# Flyback_schematic.net
KiCad netlist of a schematic drawn in Altium Designer
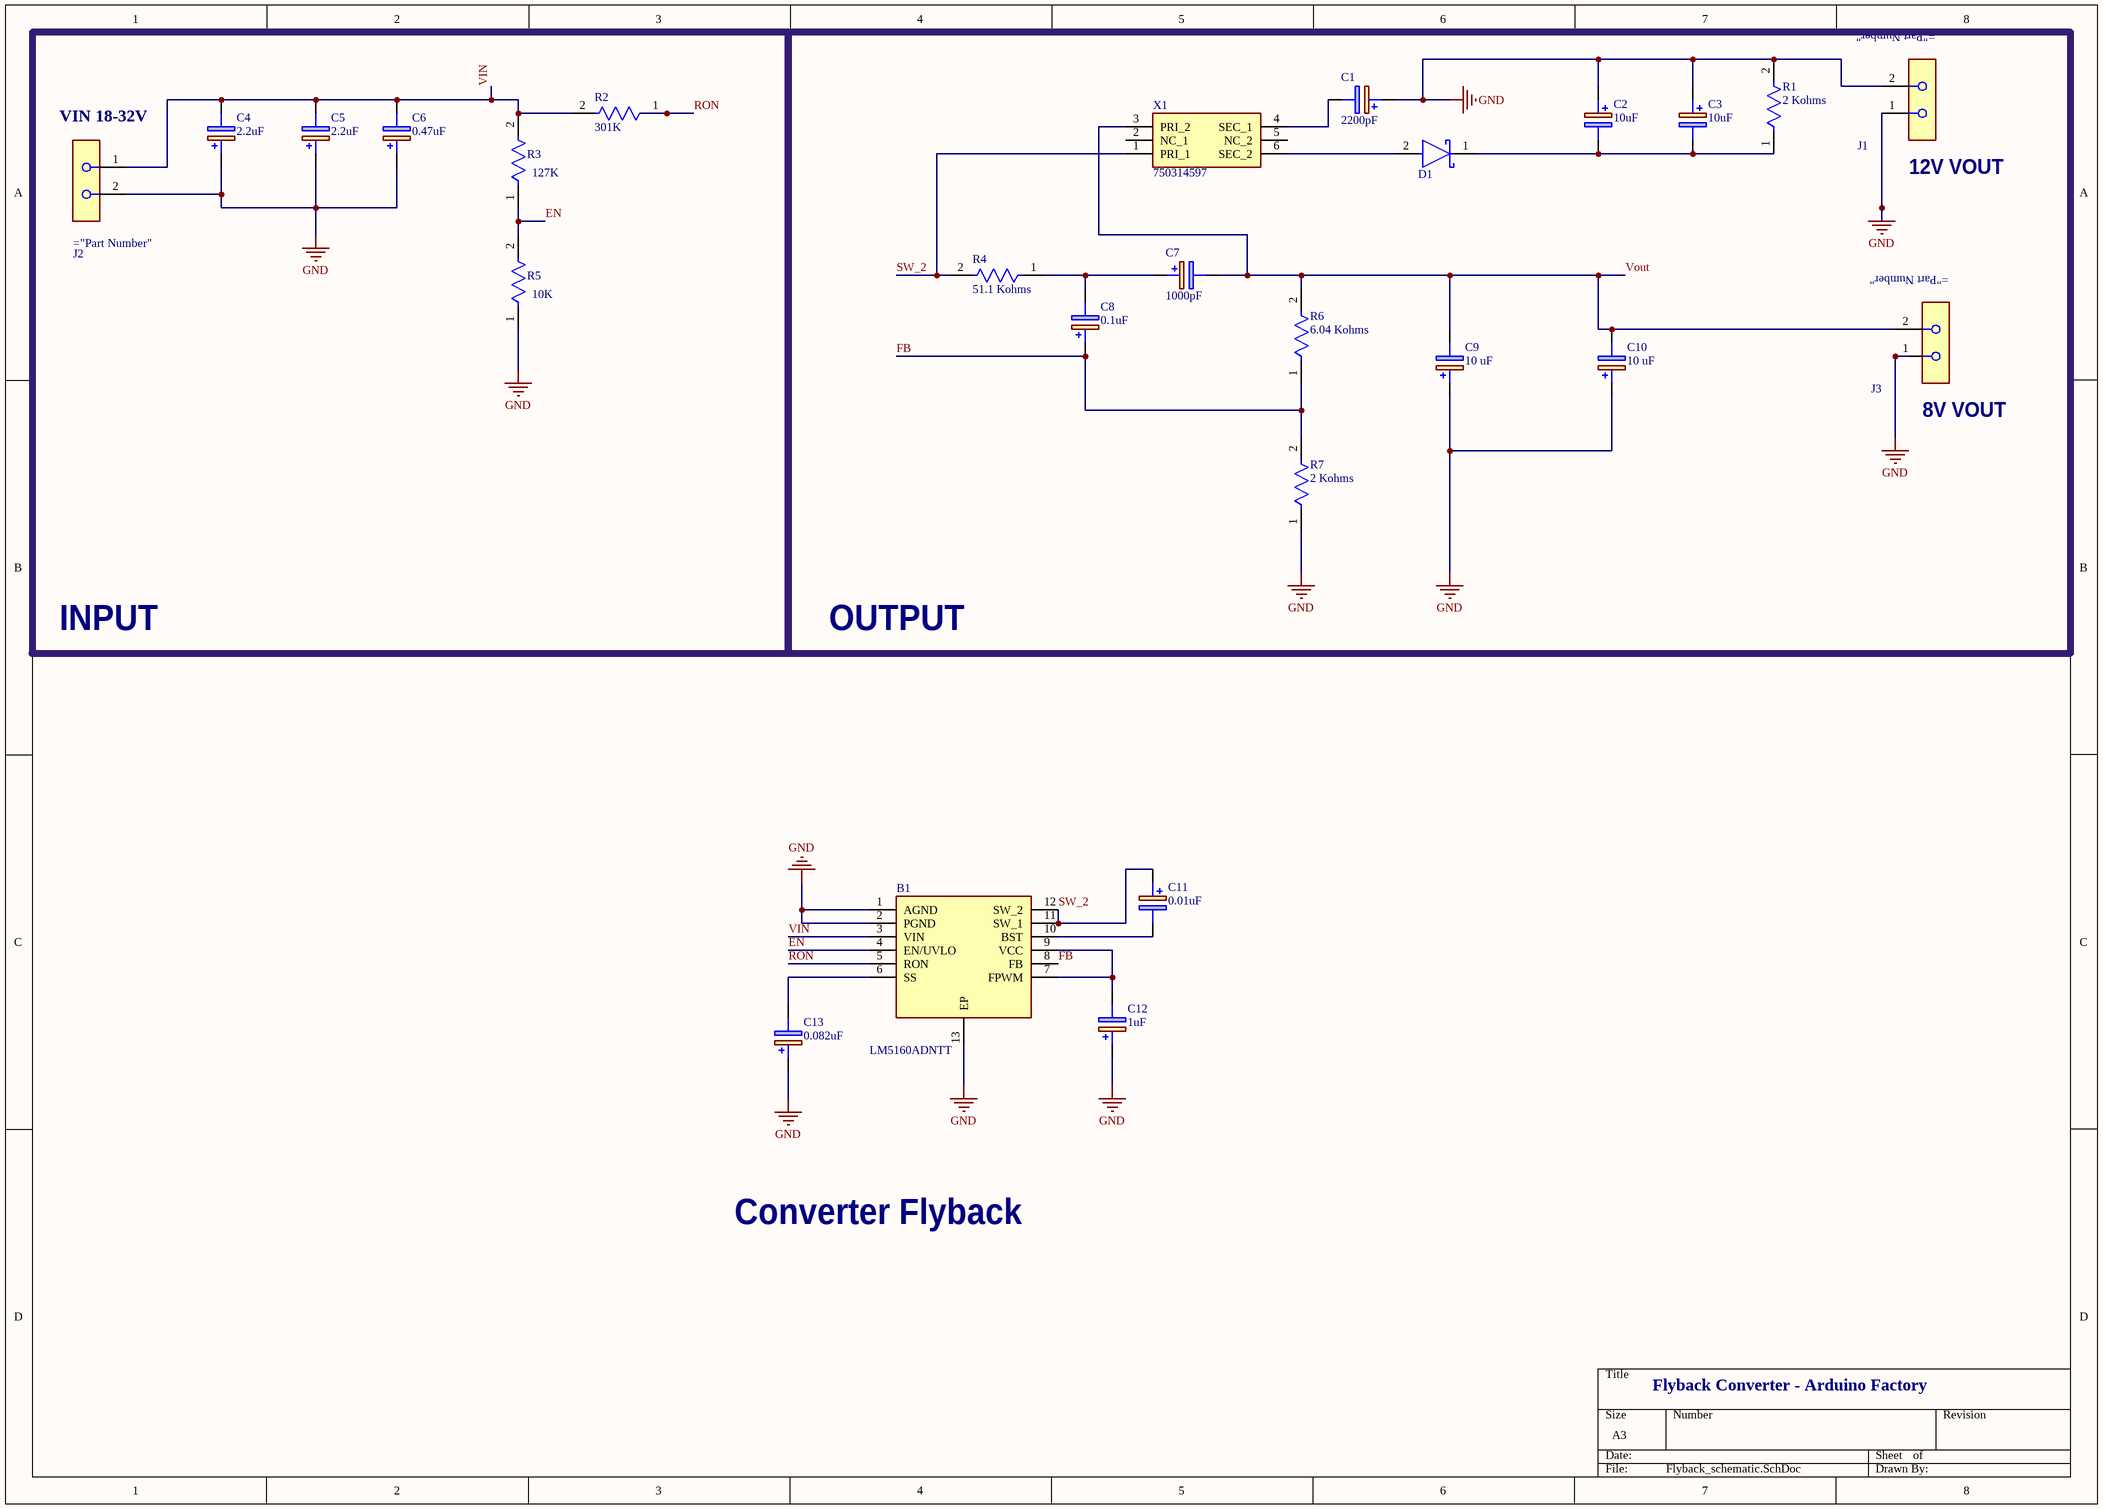
[diagram p0: Flyback_schematic.SchDoc]

(export (version "E")
  (design (tool "Eeschema 10.0.6"))
  (components
    (comp (ref "B1")
      (value "LM5160ADNTT")
      (footprint "SON50P400X400X100-13N")
      (description "LM5160A Wide Input 65V, 2A Synchronous Buck / Fly-Buck Converter")
      (fields (field (name "MOUSER PART NUMBER") "595-LM5160ADNTT"))
      (libsource (lib "LM5160ADNTT") (part "LM5160ADNTT"))
    )
    (comp (ref "C1")
      (value "2200pF")
      (footprint "CAPPRD500W60D1000H1350")
      (description "220 F 50 V Aluminum Electrolytic Capacitors Radial, Can 2000 Hrs @ 85C")
      (fields
        (field (name "MANUFACTURER_PART_NUMBER") "ESK227M050AH1EA")
        (field (name "MOUSER PART NUMBER") "80-ESK227M050AH1EA")
      )
      (libsource (lib "") (part "ESK227M050AH1EA_1"))
    )
    (comp (ref "C2")
      (value "10uF")
      (footprint "CAPPRD500W60D1000H1350")
      (description "220 F 50 V Aluminum Electrolytic Capacitors Radial, Can 2000 Hrs @ 85C")
      (fields
        (field (name "MANUFACTURER_PART_NUMBER") "ESK227M050AH1EA")
        (field (name "MOUSER PART NUMBER") "80-ESK227M050AH1EA")
      )
      (libsource (lib "") (part "ESK227M050AH1EA_2"))
    )
    (comp (ref "C3")
      (value "10uF")
      (footprint "CAPPRD500W60D1000H1350")
      (description "220 F 50 V Aluminum Electrolytic Capacitors Radial, Can 2000 Hrs @ 85C")
      (fields
        (field (name "MANUFACTURER_PART_NUMBER") "ESK227M050AH1EA")
        (field (name "MOUSER PART NUMBER") "80-ESK227M050AH1EA")
      )
      (libsource (lib "") (part "ESK227M050AH1EA_2"))
    )
    (comp (ref "C4")
      (value "2.2uF")
      (footprint "Vishay_561R_0")
      (description "220 F 50 V Aluminum Electrolytic Capacitors Radial, Can 2000 Hrs @ 85C")
      (fields
        (field (name "MANUFACTURER_PART_NUMBER") "ESK227M050AH1EA")
        (field (name "MOUSER PART NUMBER") "80-ESK227M050AH1EA")
      )
      (libsource (lib "ESK227M050AH1EA") (part "ESK227M050AH1EA"))
    )
    (comp (ref "C5")
      (value "2.2uF")
      (footprint "Vishay_561R_0")
      (description "220 F 50 V Aluminum Electrolytic Capacitors Radial, Can 2000 Hrs @ 85C")
      (fields
        (field (name "MANUFACTURER_PART_NUMBER") "ESK227M050AH1EA")
        (field (name "MOUSER PART NUMBER") "80-ESK227M050AH1EA")
      )
      (libsource (lib "ESK227M050AH1EA") (part "ESK227M050AH1EA"))
    )
    (comp (ref "C6")
      (value "0.47uF")
      (footprint "CAPPRD200W50D550H1250")
      (description "220 F 50 V Aluminum Electrolytic Capacitors Radial, Can 2000 Hrs @ 85C")
      (fields
        (field (name "MANUFACTURER_PART_NUMBER") "ESK227M050AH1EA")
        (field (name "MOUSER PART NUMBER") "80-ESK227M050AH1EA")
      )
      (libsource (lib "ESK227M050AH1EA") (part "ESK227M050AH1EA"))
    )
    (comp (ref "C7")
      (value "1000pF")
      (footprint "CAPPRD500W60D1000H1350")
      (description "220 F 50 V Aluminum Electrolytic Capacitors Radial, Can 2000 Hrs @ 85C")
      (fields
        (field (name "MANUFACTURER_PART_NUMBER") "ESK227M050AH1EA")
        (field (name "MOUSER PART NUMBER") "80-ESK227M050AH1EA")
      )
      (libsource (lib "") (part "ESK227M050AH1EA_3"))
    )
    (comp (ref "C8")
      (value "0.1uF")
      (footprint "CAPPRD500W60D1000H1350")
      (description "220 F 50 V Aluminum Electrolytic Capacitors Radial, Can 2000 Hrs @ 85C")
      (fields
        (field (name "MANUFACTURER_PART_NUMBER") "ESK227M050AH1EA")
        (field (name "MOUSER PART NUMBER") "80-ESK227M050AH1EA")
      )
      (libsource (lib "ESK227M050AH1EA") (part "ESK227M050AH1EA"))
    )
    (comp (ref "C9")
      (value "10 uF")
      (footprint "CAPPRD500W60D1000H1350")
      (description "220 F 50 V Aluminum Electrolytic Capacitors Radial, Can 2000 Hrs @ 85C")
      (fields
        (field (name "MANUFACTURER_PART_NUMBER") "ESK227M050AH1EA")
        (field (name "MOUSER PART NUMBER") "80-ESK227M050AH1EA")
      )
      (libsource (lib "ESK227M050AH1EA") (part "ESK227M050AH1EA"))
    )
    (comp (ref "C10")
      (value "10 uF")
      (footprint "CAPPRD500W60D1000H1350")
      (description "220 F 50 V Aluminum Electrolytic Capacitors Radial, Can 2000 Hrs @ 85C")
      (fields
        (field (name "MANUFACTURER_PART_NUMBER") "ESK227M050AH1EA")
        (field (name "MOUSER PART NUMBER") "80-ESK227M050AH1EA")
      )
      (libsource (lib "ESK227M050AH1EA") (part "ESK227M050AH1EA"))
    )
    (comp (ref "C11")
      (value "0.01uF")
      (footprint "K104K10X7RF53H5")
      (description "220 F 50 V Aluminum Electrolytic Capacitors Radial, Can 2000 Hrs @ 85C")
      (fields
        (field (name "MANUFACTURER_PART_NUMBER") "ESK227M050AH1EA")
        (field (name "MOUSER PART NUMBER") "80-ESK227M050AH1EA")
      )
      (libsource (lib "") (part "ESK227M050AH1EA_2"))
    )
    (comp (ref "C12")
      (value "1uF")
      (footprint "CAPPRD500W60D1000H1350")
      (description "220 F 50 V Aluminum Electrolytic Capacitors Radial, Can 2000 Hrs @ 85C")
      (fields
        (field (name "MANUFACTURER_PART_NUMBER") "ESK227M050AH1EA")
        (field (name "MOUSER PART NUMBER") "80-ESK227M050AH1EA")
      )
      (libsource (lib "ESK227M050AH1EA") (part "ESK227M050AH1EA"))
    )
    (comp (ref "C13")
      (value "0.082uF")
      (footprint "CAPPRD500W60D1000H1350")
      (description "220 F 50 V Aluminum Electrolytic Capacitors Radial, Can 2000 Hrs @ 85C")
      (fields
        (field (name "MANUFACTURER_PART_NUMBER") "ESK227M050AH1EA")
        (field (name "MOUSER PART NUMBER") "80-ESK227M050AH1EA")
      )
      (libsource (lib "ESK227M050AH1EA") (part "ESK227M050AH1EA"))
    )
    (comp (ref "D1")
      (value "Diode_Diodes_DFLS1100-7_eec")
      (footprint "Diodes_DFLS1100-7_0")
      (description "DIODE SCHOTTKY 100V POWERDI123")
      (fields (field (name "PART NUMBER") "DFLS1100-7") (field (name "VOLTAGE") "100V"))
      (libsource (lib "Diode_Diodes_DFLS1100-7_eec") (part "Diode_Diodes_DFLS1100-7_eec"))
    )
    (comp (ref "J1") (value "282837-2") (footprint "TE_282837-2_0") (libsource (lib "") (part "282837-2_1")))
    (comp (ref "J2")
      (value "282837-2")
      (footprint "TE_282837-2_0")
      (libsource (lib "Conn_TE_282837-2_eec") (part "282837-2"))
    )
    (comp (ref "J3") (value "282837-2") (footprint "TE_282837-2_0") (libsource (lib "") (part "282837-2_1")))
    (comp (ref "R1")
      (value "2 Kohms")
      (footprint "Stackpole_Electronics_Inc._CF14JT1K00_0")
      (libsource (lib "Res_Yageo_MF0207FTE52-10K_eec") (part "MF0207FTE52-10K"))
    )
    (comp (ref "R2")
      (value "301K")
      (footprint "Stackpole_Electronics_Inc._CF14JT1K00_0")
      (libsource (lib "Res_Yageo_MF0207FTE52-10K_eec") (part "MF0207FTE52-10K"))
    )
    (comp (ref "R3")
      (value "127K")
      (footprint "Stackpole_Electronics_Inc._CF14JT1K00_0")
      (libsource (lib "Res_Yageo_MF0207FTE52-10K_eec") (part "MF0207FTE52-10K"))
    )
    (comp (ref "R4")
      (value "51.1 Kohms")
      (footprint "Stackpole_Electronics_Inc._CF14JT1K00_0")
      (libsource (lib "Res_Yageo_MF0207FTE52-10K_eec") (part "MF0207FTE52-10K"))
    )
    (comp (ref "R5")
      (value "10K")
      (footprint "Stackpole_Electronics_Inc._CF14JT1K00_0")
      (libsource (lib "Res_Yageo_MF0207FTE52-10K_eec") (part "MF0207FTE52-10K"))
    )
    (comp (ref "R6")
      (value "6.04 Kohms")
      (footprint "Stackpole_Electronics_Inc._CF14JT1K00_0")
      (libsource (lib "Res_Yageo_MF0207FTE52-10K_eec") (part "MF0207FTE52-10K"))
    )
    (comp (ref "R7")
      (value "2 Kohms")
      (footprint "Stackpole_Electronics_Inc._CF14JT1K00_0")
      (libsource (lib "Res_Yageo_MF0207FTE52-10K_eec") (part "MF0207FTE52-10K"))
    )
    (comp (ref "X1")
      (value "750314597")
      (footprint "750314597")
      (description "Power Transformers MID-ITIFBK 3.87W SMD Power Transformer")
      (fields (field (name "MOUSER PART NUMBER") "710-750314597"))
      (libsource (lib "750314597") (part "750314597"))
    )
  )
  (nets
    (net (code "1") (name "/EN") (class "Default")
      (node (ref "B1") (pin "4") (pinfunction "EN/UVLO_4") (pintype "passive"))
      (node (ref "R3") (pin "1") (pinfunction "1_1") (pintype "passive"))
      (node (ref "R5") (pin "2") (pinfunction "2_2") (pintype "passive"))
    )
    (net (code "2") (name "/FB") (class "Default")
      (node (ref "B1") (pin "8") (pinfunction "FB_8") (pintype "passive"))
      (node (ref "C8") (pin "1") (pinfunction "+_1") (pintype "passive"))
      (node (ref "R6") (pin "1") (pinfunction "1_1") (pintype "passive"))
      (node (ref "R7") (pin "2") (pinfunction "2_2") (pintype "passive"))
    )
    (net (code "3") (name "/RON") (class "Default")
      (node (ref "B1") (pin "5") (pinfunction "RON_5") (pintype "passive"))
      (node (ref "R2") (pin "1") (pinfunction "1_1") (pintype "passive"))
    )
    (net (code "4") (name "/SW_2") (class "Default")
      (node (ref "B1") (pin "11") (pinfunction "SW_1_11") (pintype "passive"))
      (node (ref "B1") (pin "12") (pinfunction "SW_2_12") (pintype "passive"))
      (node (ref "C11") (pin "1") (pinfunction "+_1") (pintype "passive"))
      (node (ref "R4") (pin "2") (pinfunction "2_2") (pintype "passive"))
      (node (ref "X1") (pin "1") (pinfunction "PRI_1_1") (pintype "passive"))
    )
    (net (code "5") (name "/VIN") (class "Default")
      (node (ref "B1") (pin "3") (pinfunction "VIN_3") (pintype "passive"))
      (node (ref "C4") (pin "2") (pinfunction "-_2") (pintype "passive"))
      (node (ref "C5") (pin "2") (pinfunction "-_2") (pintype "passive"))
      (node (ref "C6") (pin "2") (pinfunction "-_2") (pintype "passive"))
      (node (ref "J2") (pin "1") (pinfunction "1_1") (pintype "passive"))
      (node (ref "R2") (pin "2") (pinfunction "2_2") (pintype "passive"))
      (node (ref "R3") (pin "2") (pinfunction "2_2") (pintype "passive"))
    )
    (net (code "6") (name "/Vout") (class "Default")
      (node (ref "C10") (pin "2") (pinfunction "-_2") (pintype "passive"))
      (node (ref "C7") (pin "2") (pinfunction "-_2") (pintype "passive"))
      (node (ref "C9") (pin "2") (pinfunction "-_2") (pintype "passive"))
      (node (ref "J3") (pin "2") (pinfunction "2_2") (pintype "passive"))
      (node (ref "R6") (pin "2") (pinfunction "2_2") (pintype "passive"))
      (node (ref "X1") (pin "3") (pinfunction "PRI_2_3") (pintype "passive"))
    )
    (net (code "7") (name "GND") (class "Default")
      (node (ref "B1") (pin "1") (pinfunction "AGND_1") (pintype "passive"))
      (node (ref "B1") (pin "13") (pinfunction "EP_13") (pintype "passive"))
      (node (ref "B1") (pin "2") (pinfunction "PGND_2") (pintype "passive"))
      (node (ref "C1") (pin "1") (pinfunction "+_1") (pintype "passive"))
      (node (ref "C10") (pin "1") (pinfunction "+_1") (pintype "passive"))
      (node (ref "C12") (pin "1") (pinfunction "+_1") (pintype "passive"))
      (node (ref "C13") (pin "1") (pinfunction "+_1") (pintype "passive"))
      (node (ref "C2") (pin "1") (pinfunction "+_1") (pintype "passive"))
      (node (ref "C3") (pin "1") (pinfunction "+_1") (pintype "passive"))
      (node (ref "C4") (pin "1") (pinfunction "+_1") (pintype "passive"))
      (node (ref "C5") (pin "1") (pinfunction "+_1") (pintype "passive"))
      (node (ref "C6") (pin "1") (pinfunction "+_1") (pintype "passive"))
      (node (ref "C9") (pin "1") (pinfunction "+_1") (pintype "passive"))
      (node (ref "J1") (pin "1") (pinfunction "1_1") (pintype "passive"))
      (node (ref "J1") (pin "2") (pinfunction "2_2") (pintype "passive"))
      (node (ref "J2") (pin "2") (pinfunction "2_2") (pintype "passive"))
      (node (ref "J3") (pin "1") (pinfunction "1_1") (pintype "passive"))
      (node (ref "R1") (pin "2") (pinfunction "2_2") (pintype "passive"))
      (node (ref "R5") (pin "1") (pinfunction "1_1") (pintype "passive"))
      (node (ref "R7") (pin "1") (pinfunction "1_1") (pintype "passive"))
    )
    (net (code "8") (name "Net-(B1-BST)") (class "Default")
      (node (ref "B1") (pin "10") (pinfunction "BST_10") (pintype "passive"))
      (node (ref "C11") (pin "2") (pinfunction "-_2") (pintype "passive"))
    )
    (net (code "9") (name "Net-(B1-FPWM)") (class "Default")
      (node (ref "B1") (pin "7") (pinfunction "FPWM_7") (pintype "passive"))
      (node (ref "B1") (pin "9") (pinfunction "VCC_9") (pintype "passive"))
      (node (ref "C12") (pin "2") (pinfunction "-_2") (pintype "passive"))
    )
    (net (code "10") (name "Net-(B1-SS)") (class "Default")
      (node (ref "B1") (pin "6") (pinfunction "SS_6") (pintype "passive"))
      (node (ref "C13") (pin "2") (pinfunction "-_2") (pintype "passive"))
    )
    (net (code "11") (name "Net-(C1--)") (class "Default")
      (node (ref "C1") (pin "2") (pinfunction "-_2") (pintype "passive"))
      (node (ref "X1") (pin "4") (pinfunction "SEC_1_4") (pintype "passive"))
    )
    (net (code "12") (name "Net-(C2--)") (class "Default")
      (node (ref "C2") (pin "2") (pinfunction "-_2") (pintype "passive"))
      (node (ref "C3") (pin "2") (pinfunction "-_2") (pintype "passive"))
      (node (ref "D1") (pin "1") (pinfunction "C_1") (pintype "passive"))
      (node (ref "R1") (pin "1") (pinfunction "1_1") (pintype "passive"))
    )
    (net (code "13") (name "Net-(C7-+)") (class "Default")
      (node (ref "C7") (pin "1") (pinfunction "+_1") (pintype "passive"))
      (node (ref "C8") (pin "2") (pinfunction "-_2") (pintype "passive"))
      (node (ref "R4") (pin "1") (pinfunction "1_1") (pintype "passive"))
    )
    (net (code "14") (name "Net-(D1-A)") (class "Default")
      (node (ref "D1") (pin "2") (pinfunction "A_2") (pintype "passive"))
      (node (ref "X1") (pin "6") (pinfunction "SEC_2_6") (pintype "passive"))
    )
    (net (code "15") (name "unconnected-(X1-NC_1-Pad2)") (class "Default")
      (node (ref "X1") (pin "2") (pinfunction "NC_1_2") (pintype "passive"))
    )
    (net (code "16") (name "unconnected-(X1-NC_2-Pad5)") (class "Default")
      (node (ref "X1") (pin "5") (pinfunction "NC_2_5") (pintype "passive"))
    )
  )
)
